# pxs2.net
KiCad netlist of a schematic drawn in EAGLE
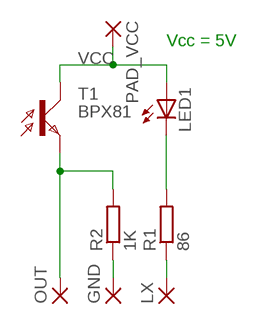
[diagram p0: schematic, sheet 1]

(export (version "E")
  (design (tool "Eeschema 10.0.6"))
  (components
    (comp (ref "GND")
      (value "SMD2")
      (footprint "eagle-import:SMD1,27-2,54")
      (libsource (lib "eagle-import") (part "SMD2"))
    )
    (comp (ref "LED1")
      (value "LED5MM")
      (footprint "eagle-import:LED5MM")
      (libsource (lib "eagle-import") (part "LED5MM"))
    )
    (comp (ref "LX")
      (value "SMD2")
      (footprint "eagle-import:SMD1,27-2,54")
      (libsource (lib "eagle-import") (part "SMD2"))
    )
    (comp (ref "OUT")
      (value "SMD2")
      (footprint "eagle-import:SMD1,27-2,54")
      (libsource (lib "eagle-import") (part "SMD2"))
    )
    (comp (ref "PAD_VCC")
      (value "SMD2")
      (footprint "eagle-import:SMD1,27-2,54")
      (libsource (lib "eagle-import") (part "SMD2"))
    )
    (comp (ref "R1")
      (value "86")
      (footprint "eagle-import:0207_2V")
      (libsource (lib "eagle-import") (part "R-EU_0207/2V"))
    )
    (comp (ref "R2")
      (value "1K")
      (footprint "eagle-import:R1206")
      (libsource (lib "eagle-import") (part "R-EU_R1206"))
    )
    (comp (ref "T1")
      (value "BPX81")
      (footprint "eagle-import:BPX81")
      (libsource (lib "eagle-import") (part "BPX81"))
    )
  )
  (nets
    (net (code "1") (name "/VCC") (class "Default")
      (node (ref "LED1") (pin "A") (pinfunction "A_A") (pintype "passive"))
      (node (ref "PAD_VCC") (pin "1") (pinfunction "P_1") (pintype "passive"))
      (node (ref "T1") (pin "C") (pinfunction "C_C") (pintype "passive"))
    )
    (net (code "2") (name "Net-(GND-P)") (class "Default")
      (node (ref "GND") (pin "1") (pinfunction "P_1") (pintype "passive"))
      (node (ref "R2") (pin "1") (pinfunction "1_1") (pintype "passive"))
    )
    (net (code "3") (name "Net-(LED1-C)") (class "Default")
      (node (ref "LED1") (pin "K") (pinfunction "C_K") (pintype "passive"))
      (node (ref "R1") (pin "2") (pinfunction "2_2") (pintype "passive"))
    )
    (net (code "4") (name "Net-(LX-P)") (class "Default")
      (node (ref "LX") (pin "1") (pinfunction "P_1") (pintype "passive"))
      (node (ref "R1") (pin "1") (pinfunction "1_1") (pintype "passive"))
    )
    (net (code "5") (name "Net-(OUT-P)") (class "Default")
      (node (ref "OUT") (pin "1") (pinfunction "P_1") (pintype "passive"))
      (node (ref "R2") (pin "2") (pinfunction "2_2") (pintype "passive"))
      (node (ref "T1") (pin "E") (pinfunction "E_E") (pintype "passive"))
    )
  )
)
